# BMS_Carrier_-_AFE_Interface.net
KiCad netlist of a schematic drawn in Altium Designer
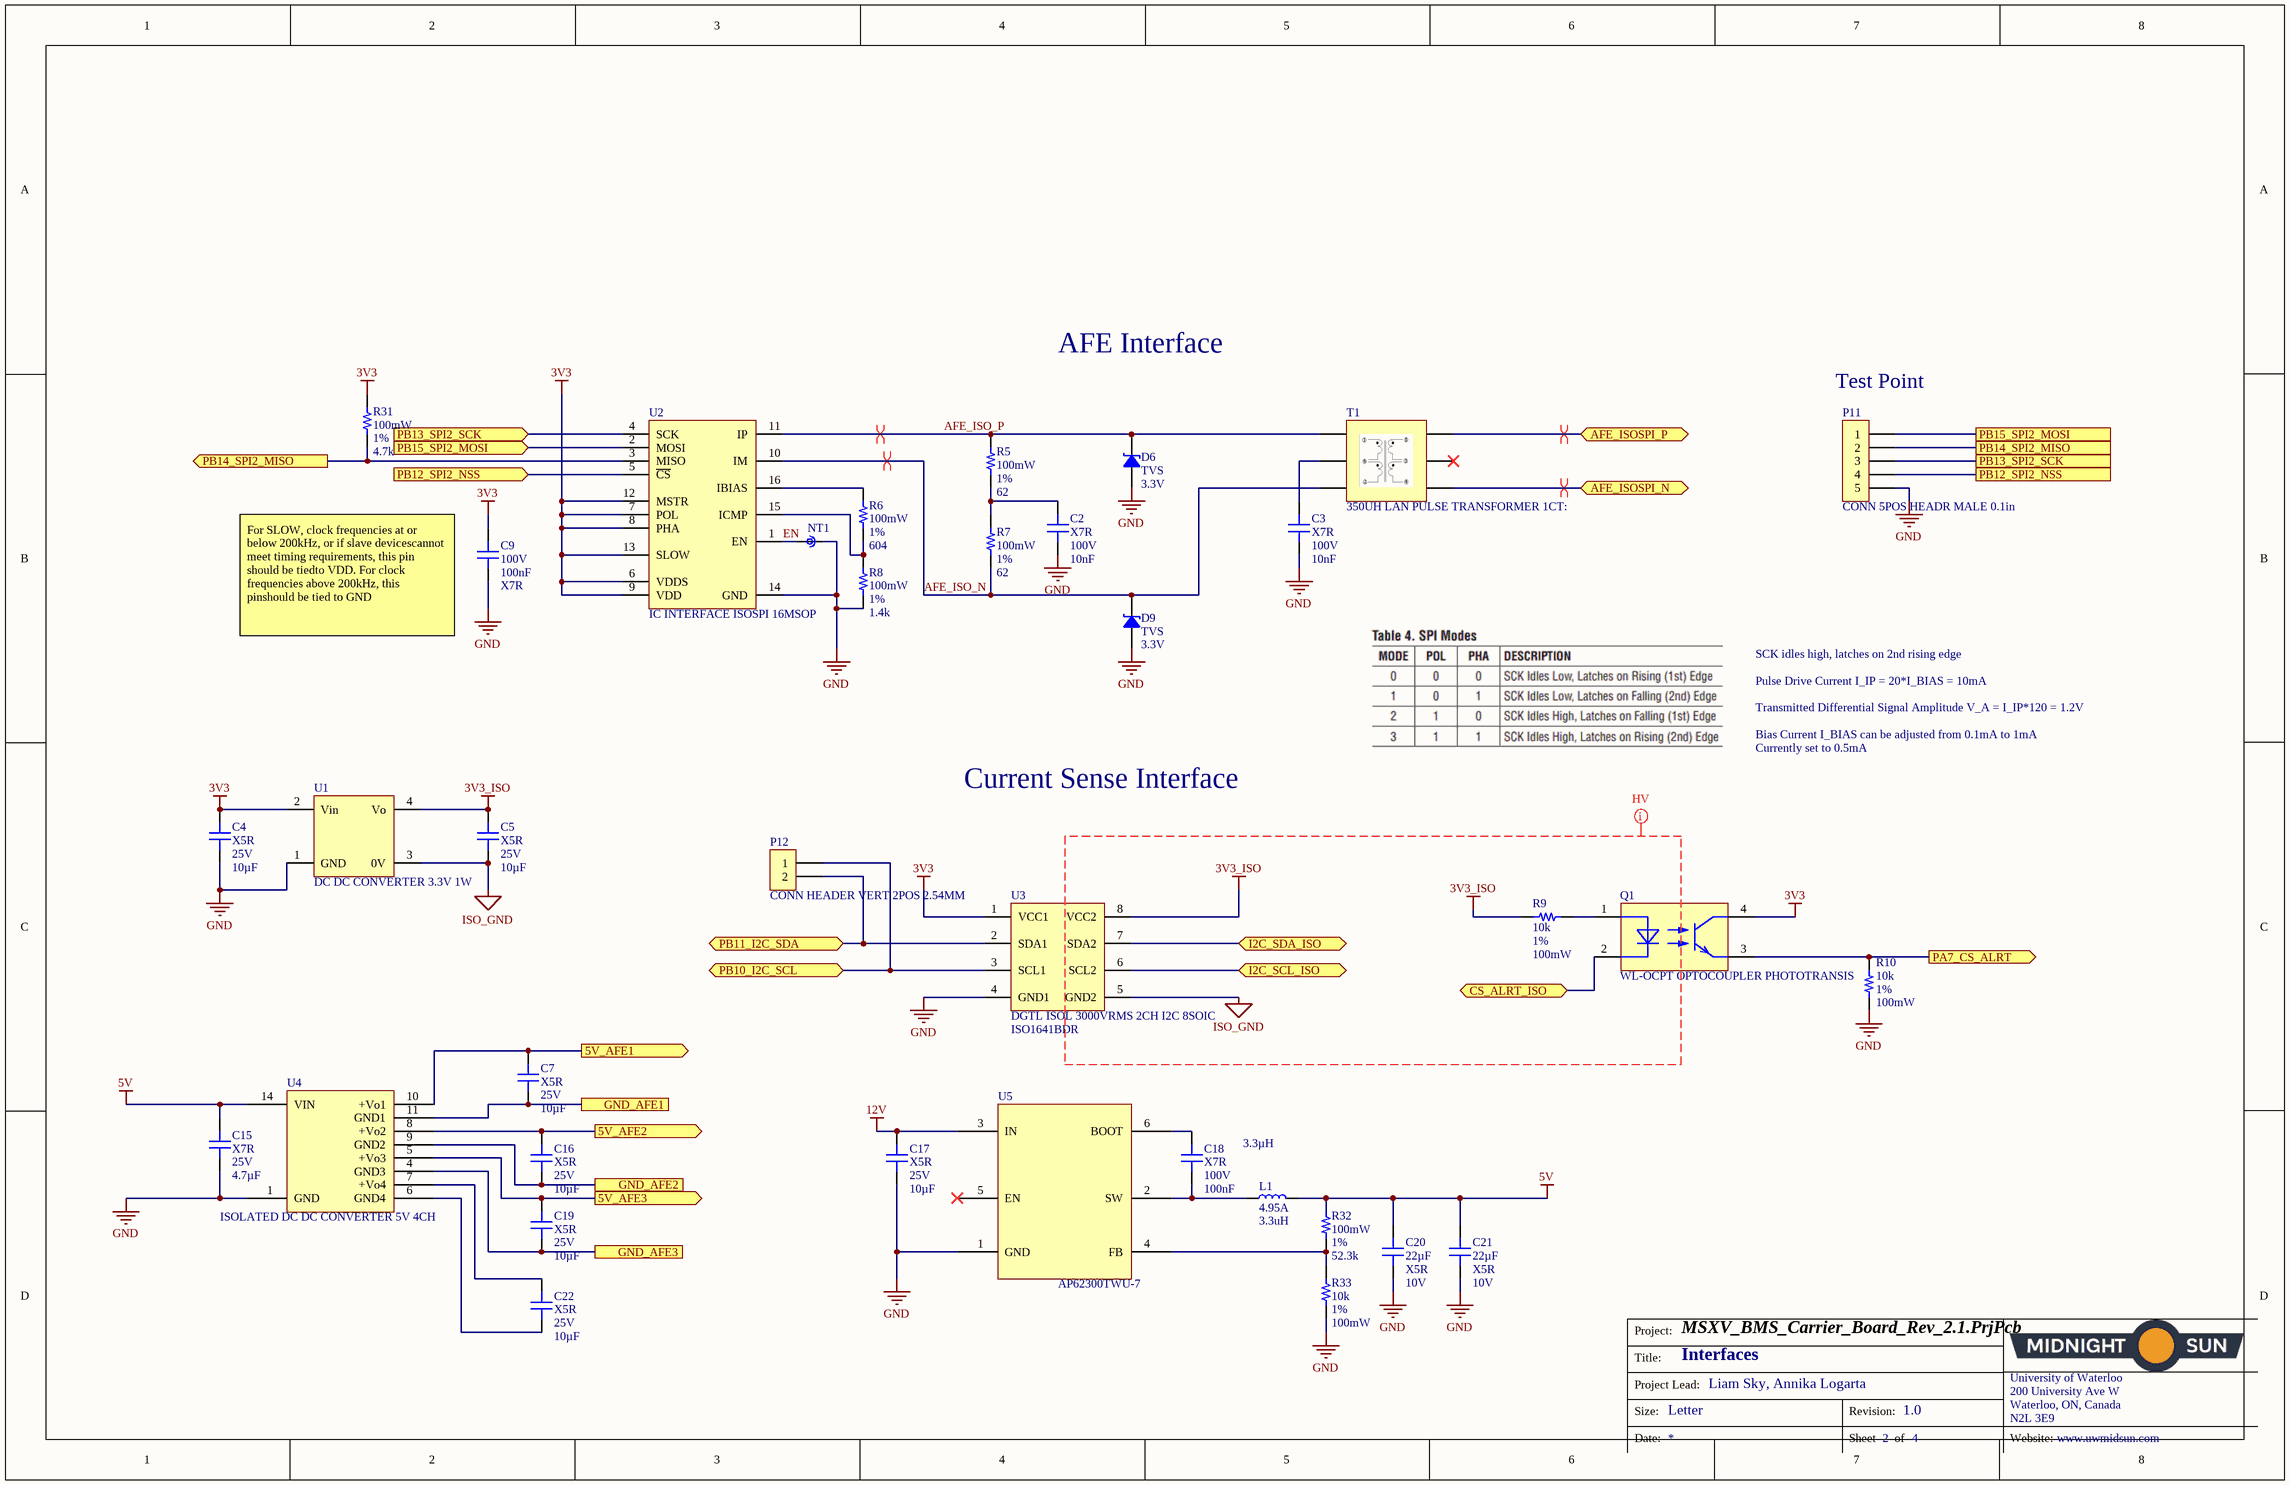
[diagram p0: BMS Carrier - AFE Interface.SchDoc]

(export (version "E")
  (design (tool "Eeschema 10.0.6"))
  (components
    (comp (ref "C2")
      (value "CAP CER 10NF 100V 10% X7R 0603")
      (footprint "CAP 0603_1608")
      (fields
        (field (name "DIELECTRIC CODE") "X7R")
        (field (name "VOLTAGE RATING") "100V")
        (field (name "CAPACITANCE") "10nF")
        (field (name "TOLERANCE") "10%")
      )
      (libsource (lib "Midnight Sun") (part "Capacitor"))
    )
    (comp (ref "C3")
      (value "CAP CER 10NF 100V 10% X7R 0603")
      (footprint "CAP 0603_1608")
      (fields
        (field (name "DIELECTRIC CODE") "X7R")
        (field (name "VOLTAGE RATING") "100V")
        (field (name "CAPACITANCE") "10nF")
        (field (name "TOLERANCE") "10%")
      )
      (libsource (lib "Midnight Sun") (part "Capacitor"))
    )
    (comp (ref "C4")
      (value "CAP CER 10UF 25V 20% X5R 0603")
      (footprint "CAP 0603_1608")
      (description "10µF ±20% 25V Ceramic Capacitor X5R 0603 (1608 Metric)")
      (fields
        (field (name "DIELECTRIC CODE") "X5R")
        (field (name "VOLTAGE RATING") "25V")
        (field (name "CAPACITANCE") "10µF")
        (field (name "TOLERANCE") "20%")
      )
      (libsource (lib "Midnight Sun") (part "Capacitor"))
    )
    (comp (ref "C5")
      (value "CAP CER 10UF 25V 20% X5R 0603")
      (footprint "CAP 0603_1608")
      (description "10µF ±20% 25V Ceramic Capacitor X5R 0603 (1608 Metric)")
      (fields
        (field (name "DIELECTRIC CODE") "X5R")
        (field (name "VOLTAGE RATING") "25V")
        (field (name "CAPACITANCE") "10µF")
        (field (name "TOLERANCE") "20%")
      )
      (libsource (lib "Midnight Sun") (part "Capacitor"))
    )
    (comp (ref "C7")
      (value "CAP CER 10UF 25V 20% X5R 0603")
      (footprint "CAP 0603_1608")
      (description "10µF ±20% 25V Ceramic Capacitor X5R 0603 (1608 Metric)")
      (fields
        (field (name "DIELECTRIC CODE") "X5R")
        (field (name "VOLTAGE RATING") "25V")
        (field (name "CAPACITANCE") "10µF")
        (field (name "TOLERANCE") "20%")
      )
      (libsource (lib "Midnight Sun") (part "Capacitor"))
    )
    (comp (ref "C9")
      (value "CAP CER 0.1UF 100V 10% X7R 0603")
      (footprint "CAP 0603_1608")
      (fields
        (field (name "TOLERANCE") "10%")
        (field (name "VOLTAGE RATING") "100V")
        (field (name "CAPACITANCE") "100nF")
        (field (name "DIELECTRIC CODE") "X7R")
      )
      (libsource (lib "Midnight Sun") (part "Capacitor"))
    )
    (comp (ref "C15")
      (value "CAP CER 4.7UF 25V 10% X5R 0603")
      (footprint "CAP 0603_1608")
      (description "4.7µF ±10% 25V Ceramic Capacitor X5R 0603 (1608 Metric)")
      (fields
        (field (name "DIELECTRIC CODE") "X7R")
        (field (name "VOLTAGE RATING") "25V")
        (field (name "CAPACITANCE") "4.7µF")
        (field (name "TOLERANCE") "10%")
      )
      (libsource (lib "Midnight Sun") (part "Capacitor"))
    )
    (comp (ref "C16")
      (value "CAP CER 10UF 25V 20% X5R 0603")
      (footprint "CAP 0603_1608")
      (description "10µF ±20% 25V Ceramic Capacitor X5R 0603 (1608 Metric)")
      (fields
        (field (name "DIELECTRIC CODE") "X5R")
        (field (name "VOLTAGE RATING") "25V")
        (field (name "CAPACITANCE") "10µF")
        (field (name "TOLERANCE") "20%")
      )
      (libsource (lib "Midnight Sun") (part "Capacitor"))
    )
    (comp (ref "C17")
      (value "CAP CER 10UF 25V 20% X5R 0603")
      (footprint "CAP 0603_1608")
      (description "10µF ±20% 25V Ceramic Capacitor X5R 0603 (1608 Metric)")
      (fields
        (field (name "DIELECTRIC CODE") "X5R")
        (field (name "VOLTAGE RATING") "25V")
        (field (name "CAPACITANCE") "10µF")
        (field (name "TOLERANCE") "20%")
      )
      (libsource (lib "Midnight Sun") (part "Capacitor"))
    )
    (comp (ref "C18")
      (value "CAP CER 0.1UF 100V 10% X7R 0603")
      (footprint "CAP 0603_1608")
      (fields
        (field (name "DIELECTRIC CODE") "X7R")
        (field (name "VOLTAGE RATING") "100V")
        (field (name "CAPACITANCE") "100nF")
        (field (name "TOLERANCE") "10%")
      )
      (libsource (lib "Midnight Sun") (part "Capacitor"))
    )
    (comp (ref "C19")
      (value "CAP CER 10UF 25V 20% X5R 0603")
      (footprint "CAP 0603_1608")
      (description "10µF ±20% 25V Ceramic Capacitor X5R 0603 (1608 Metric)")
      (fields
        (field (name "DIELECTRIC CODE") "X5R")
        (field (name "VOLTAGE RATING") "25V")
        (field (name "CAPACITANCE") "10µF")
        (field (name "TOLERANCE") "20%")
      )
      (libsource (lib "Midnight Sun") (part "Capacitor"))
    )
    (comp (ref "C20")
      (value "CAP CER 22UF 10V 20% X5R 0603")
      (footprint "CAP 0603_1608")
      (fields
        (field (name "CAPACITANCE") "22µF")
        (field (name "TOLERANCE") "20%")
        (field (name "DIELECTRIC CODE") "X5R")
        (field (name "VOLTAGE RATING") "10V")
      )
      (libsource (lib "Midnight Sun") (part "Capacitor"))
    )
    (comp (ref "C21")
      (value "CAP CER 22UF 10V 20% X5R 0603")
      (footprint "CAP 0603_1608")
      (fields
        (field (name "CAPACITANCE") "22µF")
        (field (name "TOLERANCE") "20%")
        (field (name "DIELECTRIC CODE") "X5R")
        (field (name "VOLTAGE RATING") "10V")
      )
      (libsource (lib "Midnight Sun") (part "Capacitor"))
    )
    (comp (ref "C22")
      (value "CAP CER 10UF 25V 20% X5R 0603")
      (footprint "CAP 0603_1608")
      (description "10µF ±20% 25V Ceramic Capacitor X5R 0603 (1608 Metric)")
      (fields
        (field (name "DIELECTRIC CODE") "X5R")
        (field (name "VOLTAGE RATING") "25V")
        (field (name "CAPACITANCE") "10µF")
        (field (name "TOLERANCE") "20%")
      )
      (libsource (lib "Midnight Sun") (part "Capacitor"))
    )
    (comp (ref "D6")
      (value "TVS DIODE 3.3VWM 10VC SOD323")
      (footprint "SOD 323")
      (description "Trans Voltage Suppressor Diode, 3.3V V(RWM), Unidirectional, 1 Element, Silicon")
      (fields (field (name "TYPE") "TVS") (field (name "REVERSE BLOCKING VOLTAGE") "3.3V"))
      (libsource (lib "Midnight Sun") (part "Diode Zener/TVS"))
    )
    (comp (ref "D9")
      (value "TVS DIODE 3.3VWM 10VC SOD323")
      (footprint "SOD 323")
      (description "Trans Voltage Suppressor Diode, 3.3V V(RWM), Unidirectional, 1 Element, Silicon")
      (fields (field (name "TYPE") "TVS") (field (name "REVERSE BLOCKING VOLTAGE") "3.3V"))
      (libsource (lib "Midnight Sun") (part "Diode Zener/TVS"))
    )
    (comp (ref "L1")
      (value "3.3µH")
      (footprint "INDUCTOR TDK 6x6")
      (description "General Purpose Inductor, 3.3uH, 30%, 1 Element, Ferrite-Core, SMD, 2424")
      (fields
        (field (name "RATED CURRENT-MAX") "4.95A")
        (field (name "INDUCTANCE-NOM (L)") "3.3uH")
        (field (name "TOLERANCE") "30%")
        (field (name "Comment") "FIXED IND 3.3UH 4.95A 30MOHM SMD")
      )
      (libsource (lib "Midnight Sun") (part "FIXED IND 3.3UH 4.95A 30MOHM SMD"))
    )
    (comp (ref "NT1")
      (value "Net Tie 5mil")
      (footprint "Net Tie")
      (libsource (lib "Midnight Sun") (part "Net Tie"))
    )
    (comp (ref "P11")
      (value "CONN 5POS HEADR MALE 0.1in")
      (footprint "CONN, 5POS HEADR 0.1\"")
      (description "5 Positions Header, Breakaway Connector 0.100\" (2.54mm) Through Hole Tin")
      (fields (field (name "SOURCE") "Schematic Diagrams.SchLib"))
      (libsource (lib "Midnight Sun") (part "CONN 5POS HEADR MALE 0.1in"))
    )
    (comp (ref "P12")
      (value "CONN HEADER VERT 2POS 2.54MM")
      (footprint "HDR1X2")
      (description "Connector Header Through Hole 2 position 0.100\" (2.54mm)")
      (libsource (lib "Midnight Sun") (part "CONN 2POS"))
    )
    (comp (ref "Q1")
      (value "WL-OCPT OPTOCOUPLER PHOTOTRANSIS")
      (footprint "WL-OCPT_LSOP4")
      (description "Optocoupler, Transistor, 80V, Lsop-4 Rohs Compliant: Yes")
      (libsource (lib "Midnight Sun") (part "Optocoupler Phototransistor_DC_1 Channel"))
    )
    (comp (ref "R5")
      (value "RES 62 OHM 1% 1/10W 0603")
      (footprint "RES 0603_1608")
      (fields
        (field (name "POWER RATING") "100mW")
        (field (name "TOLERANCE") "1%")
        (field (name "RESISTANCE") "62")
      )
      (libsource (lib "Midnight Sun") (part "Resistor"))
    )
    (comp (ref "R6")
      (value "RES 604 OHM 1% 1/10W 0603")
      (footprint "RES 0603_1608")
      (fields
        (field (name "POWER RATING") "100mW")
        (field (name "TOLERANCE") "1%")
        (field (name "RESISTANCE") "604")
      )
      (libsource (lib "Midnight Sun") (part "Resistor"))
    )
    (comp (ref "R7")
      (value "RES 62 OHM 1% 1/10W 0603")
      (footprint "RES 0603_1608")
      (fields
        (field (name "POWER RATING") "100mW")
        (field (name "TOLERANCE") "1%")
        (field (name "RESISTANCE") "62")
      )
      (libsource (lib "Midnight Sun") (part "Resistor"))
    )
    (comp (ref "R8")
      (value "RES 1.4K OHM 1% 1/10W 0603")
      (footprint "RES 0603_1608")
      (fields
        (field (name "POWER RATING") "100mW")
        (field (name "TOLERANCE") "1%")
        (field (name "RESISTANCE") "1.4k")
      )
      (libsource (lib "Midnight Sun") (part "Resistor"))
    )
    (comp (ref "R9")
      (value "RES 10K OHM 1% 1/10W 0603")
      (footprint "RES 0603_1608")
      (description "10 ±1% 0.1W, 1/10W Chip Resistor 0603 (1608 Metric) Automotive AEC-Q200 Thick Film")
      (fields
        (field (name "RESISTANCE") "10k")
        (field (name "TOLERANCE") "1%")
        (field (name "POWER RATING") "100mW")
      )
      (libsource (lib "Midnight Sun") (part "Resistor"))
    )
    (comp (ref "R10")
      (value "RES 10K OHM 1% 1/10W 0603")
      (footprint "RES 0603_1608")
      (description "10 ±1% 0.1W, 1/10W Chip Resistor 0603 (1608 Metric) Automotive AEC-Q200 Thick Film")
      (fields
        (field (name "RESISTANCE") "10k")
        (field (name "TOLERANCE") "1%")
        (field (name "POWER RATING") "100mW")
      )
      (libsource (lib "Midnight Sun") (part "Resistor"))
    )
    (comp (ref "R31")
      (value "RES 4.7K OHM 1% 1/10W 0603")
      (footprint "RES 0603_1608")
      (fields
        (field (name "POWER RATING") "100mW")
        (field (name "TOLERANCE") "1%")
        (field (name "RESISTANCE") "4.7k")
      )
      (libsource (lib "Midnight Sun") (part "Resistor"))
    )
    (comp (ref "R32")
      (value "RES 52.3K OHM 1% 1/10W 0603")
      (footprint "RES 0603_1608")
      (fields
        (field (name "POWER RATING") "100mW")
        (field (name "TOLERANCE") "1%")
        (field (name "RESISTANCE") "52.3k")
      )
      (libsource (lib "Midnight Sun") (part "Resistor"))
    )
    (comp (ref "R33")
      (value "RES 10K OHM 1% 1/10W 0603")
      (footprint "RES 0603_1608")
      (description "10 ±1% 0.1W, 1/10W Chip Resistor 0603 (1608 Metric) Automotive AEC-Q200 Thick Film")
      (fields
        (field (name "RESISTANCE") "10k")
        (field (name "TOLERANCE") "1%")
        (field (name "POWER RATING") "100mW")
      )
      (libsource (lib "Midnight Sun") (part "Resistor"))
    )
    (comp (ref "T1")
      (value "350UH LAN PULSE TRANSFORMER 1CT:")
      (footprint "TXF453229NF-121-Footprint-1")
      (description "350µH LAN Pulse Transformer 1:1 Surface Mount")
      (libsource (lib "Midnight Sun") (part "TXF453229NF-121"))
    )
    (comp (ref "U1")
      (value "DC DC CONVERTER 3.3V 1W")
      (footprint "DCDC ISOLATED 12V 1W-Footprint-1")
      (description "DC DC Converter 3.3V 1W")
      (libsource (lib "Midnight Sun") (part "DCDC ISOLATED 3.3V 1W"))
    )
    (comp (ref "U2")
      (value "IC INTERFACE ISOSPI 16MSOP")
      (footprint "MSOP 16")
      (description "Isolated Communications Interface 3.3V/5V Automotive 16-Pin MSOP Tube")
      (fields (field (name "MANUFACTURER PART NUMBER") "LTC6820IMS#PBF"))
      (libsource (lib "Midnight Sun") (part "LT-LTC6820-MS-16"))
    )
    (comp (ref "U3")
      (value "DGTL ISOL 3000VRMS 2CH I2C 8SOIC")
      (footprint "SOIC 8")
      (description "I²C Digital Isolator 3000Vrms 2 Channel 1Mbps 50kV/µs CMTI 8-SOIC (0.154\", 3.90mm Width)")
      (fields (field (name "MANUFACTURER PART NUMBER") "ISO1641BDR"))
      (libsource (lib "Midnight Sun") (part "DGTL ISOL 2500VRMS 2CH I2C 8SOIC-Symbol-1"))
    )
    (comp (ref "U4")
      (value "ISOLATED DC DC CONVERTER 5V 4CH")
      (footprint "DIP14")
      (description "Isolated Module DC DC Converter 4 Output 5V 5V 5V 5V 50mA, 50mA, 50mA, 50mA 4.5V - 5.5V Input")
      (libsource (lib "Midnight Sun") (part "J0505N-1WR3"))
    )
    (comp (ref "U5")
      (value "CMP-031-00049-1")
      (footprint "TSOT26")
      (description "Buck Switching Regulator IC Positive Adjustable 0.8V 1 Output 3A SOT-23-6 Thin, TSOT-23-6")
      (fields (field (name "MANUFACTURER") "Diodes") (field (name "MANUFACTURER PART NUMBER") "AP62300TWU-7"))
      (libsource (lib "Midnight Sun") (part "IC REG BUCK ADJ 3A TSOT26"))
    )
  )
  (nets
    (net (code "1") (name "/5V_AFE1") (class "Default")
      (node (ref "C7") (pin "2") (pinfunction "2_2") (pintype "passive"))
      (node (ref "U4") (pin "10") (pinfunction "+Vo1_10") (pintype "passive"))
    )
    (net (code "2") (name "/5V_AFE2") (class "Default")
      (node (ref "C16") (pin "2") (pinfunction "2_2") (pintype "passive"))
      (node (ref "U4") (pin "8") (pinfunction "+Vo2_8") (pintype "passive"))
    )
    (net (code "3") (name "/5V_AFE3") (class "Default")
      (node (ref "C19") (pin "2") (pinfunction "2_2") (pintype "passive"))
      (node (ref "U4") (pin "5") (pinfunction "+Vo3_5") (pintype "passive"))
    )
    (net (code "4") (name "/AFE_ISOSPI_N") (class "Default")
      (node (ref "T1") (pin "4") (pinfunction "2_4") (pintype "passive"))
    )
    (net (code "5") (name "/AFE_ISOSPI_P") (class "Default")
      (node (ref "T1") (pin "5") (pinfunction "0_5") (pintype "passive"))
    )
    (net (code "6") (name "/AFE_ISO_N") (class "Default")
      (node (ref "D9") (pin "1") (pinfunction "1_1") (pintype "passive"))
      (node (ref "R7") (pin "1") (pinfunction "1_1") (pintype "passive"))
      (node (ref "T1") (pin "2") (pinfunction "5_2") (pintype "passive"))
      (node (ref "U2") (pin "10") (pinfunction "IM_10") (pintype "passive"))
    )
    (net (code "7") (name "/AFE_ISO_P") (class "Default")
      (node (ref "D6") (pin "1") (pinfunction "1_1") (pintype "passive"))
      (node (ref "R5") (pin "2") (pinfunction "2_2") (pintype "passive"))
      (node (ref "T1") (pin "1") (pinfunction "3_1") (pintype "passive"))
      (node (ref "U2") (pin "11") (pinfunction "IP_11") (pintype "passive"))
    )
    (net (code "8") (name "/CS_ALRT_ISO") (class "Default")
      (node (ref "Q1") (pin "2") (pinfunction "Cathode_2") (pintype "passive"))
    )
    (net (code "9") (name "/EN") (class "Default")
      (node (ref "NT1") (pin "1") (pinfunction "1_1") (pintype "passive"))
      (node (ref "U2") (pin "1") (pinfunction "EN_1") (pintype "passive"))
    )
    (net (code "10") (name "/GND_AFE1") (class "Default")
      (node (ref "C7") (pin "1") (pinfunction "1_1") (pintype "passive"))
      (node (ref "U4") (pin "11") (pinfunction "GND1_11") (pintype "passive"))
    )
    (net (code "11") (name "/GND_AFE2") (class "Default")
      (node (ref "C16") (pin "1") (pinfunction "1_1") (pintype "passive"))
      (node (ref "U4") (pin "9") (pinfunction "GND2_9") (pintype "passive"))
    )
    (net (code "12") (name "/GND_AFE3") (class "Default")
      (node (ref "C19") (pin "1") (pinfunction "1_1") (pintype "passive"))
      (node (ref "U4") (pin "4") (pinfunction "GND3_4") (pintype "passive"))
    )
    (net (code "13") (name "/I2C_SCL_ISO") (class "Default")
      (node (ref "U3") (pin "6") (pinfunction "SCL2_6") (pintype "passive"))
    )
    (net (code "14") (name "/I2C_SDA_ISO") (class "Default")
      (node (ref "U3") (pin "7") (pinfunction "SDA2_7") (pintype "passive"))
    )
    (net (code "15") (name "/PA7_CS_ALRT") (class "Default")
      (node (ref "Q1") (pin "3") (pinfunction "Emitter_3") (pintype "passive"))
      (node (ref "R10") (pin "2") (pinfunction "2_2") (pintype "passive"))
    )
    (net (code "16") (name "/PB10_I2C_SCL") (class "Default")
      (node (ref "P12") (pin "1") (pinfunction "1_1") (pintype "passive"))
      (node (ref "U3") (pin "3") (pinfunction "SCL1_3") (pintype "passive"))
    )
    (net (code "17") (name "/PB11_I2C_SDA") (class "Default")
      (node (ref "P12") (pin "2") (pinfunction "2_2") (pintype "passive"))
      (node (ref "U3") (pin "2") (pinfunction "SDA1_2") (pintype "passive"))
    )
    (net (code "18") (name "/PB12_SPI2_NSS") (class "Default")
      (node (ref "P11") (pin "4") (pinfunction "4_4") (pintype "passive"))
      (node (ref "U2") (pin "5") (pinfunction "~{CS}_5") (pintype "passive"))
    )
    (net (code "19") (name "/PB13_SPI2_SCK") (class "Default")
      (node (ref "P11") (pin "3") (pinfunction "3_3") (pintype "passive"))
      (node (ref "U2") (pin "4") (pinfunction "SCK_4") (pintype "passive"))
    )
    (net (code "20") (name "/PB14_SPI2_MISO") (class "Default")
      (node (ref "P11") (pin "2") (pinfunction "2_2") (pintype "passive"))
      (node (ref "R31") (pin "2") (pinfunction "2_2") (pintype "passive"))
      (node (ref "U2") (pin "3") (pinfunction "MISO_3") (pintype "passive"))
    )
    (net (code "21") (name "/PB15_SPI2_MOSI") (class "Default")
      (node (ref "P11") (pin "1") (pinfunction "1_1") (pintype "passive"))
      (node (ref "U2") (pin "2") (pinfunction "MOSI_2") (pintype "passive"))
    )
    (net (code "22") (name "3V3") (class "Default")
      (node (ref "C4") (pin "2") (pinfunction "2_2") (pintype "passive"))
      (node (ref "C9") (pin "2") (pinfunction "2_2") (pintype "passive"))
      (node (ref "Q1") (pin "4") (pinfunction "Collector_4") (pintype "passive"))
      (node (ref "R31") (pin "1") (pinfunction "1_1") (pintype "passive"))
      (node (ref "U1") (pin "2") (pinfunction "Vin_2") (pintype "passive"))
      (node (ref "U2") (pin "12") (pinfunction "MSTR_12") (pintype "passive"))
      (node (ref "U2") (pin "13") (pinfunction "SLOW_13") (pintype "passive"))
      (node (ref "U2") (pin "6") (pinfunction "VDDS_6") (pintype "passive"))
      (node (ref "U2") (pin "7") (pinfunction "POL_7") (pintype "passive"))
      (node (ref "U2") (pin "8") (pinfunction "PHA_8") (pintype "passive"))
      (node (ref "U2") (pin "9") (pinfunction "VDD_9") (pintype "passive"))
      (node (ref "U3") (pin "1") (pinfunction "VCC1_1") (pintype "passive"))
    )
    (net (code "23") (name "3V3_ISO") (class "Default")
      (node (ref "C5") (pin "2") (pinfunction "2_2") (pintype "passive"))
      (node (ref "R9") (pin "2") (pinfunction "2_2") (pintype "passive"))
      (node (ref "U1") (pin "4") (pinfunction "Vo_4") (pintype "passive"))
      (node (ref "U3") (pin "8") (pinfunction "VCC2_8") (pintype "passive"))
    )
    (net (code "24") (name "5V") (class "Default")
      (node (ref "C15") (pin "1") (pinfunction "1_1") (pintype "passive"))
      (node (ref "C20") (pin "2") (pinfunction "2_2") (pintype "passive"))
      (node (ref "C21") (pin "2") (pinfunction "2_2") (pintype "passive"))
      (node (ref "L1") (pin "2") (pintype "passive"))
      (node (ref "R32") (pin "2") (pinfunction "2_2") (pintype "passive"))
      (node (ref "U4") (pin "14") (pinfunction "VIN_14") (pintype "passive"))
    )
    (net (code "25") (name "12V") (class "Default")
      (node (ref "C17") (pin "2") (pinfunction "2_2") (pintype "passive"))
      (node (ref "U5") (pin "3") (pinfunction "IN_3") (pintype "passive"))
    )
    (net (code "26") (name "GND") (class "Default")
      (node (ref "C15") (pin "2") (pinfunction "2_2") (pintype "passive"))
      (node (ref "C17") (pin "1") (pinfunction "1_1") (pintype "passive"))
      (node (ref "C2") (pin "1") (pinfunction "1_1") (pintype "passive"))
      (node (ref "C20") (pin "1") (pinfunction "1_1") (pintype "passive"))
      (node (ref "C21") (pin "1") (pinfunction "1_1") (pintype "passive"))
      (node (ref "C3") (pin "1") (pinfunction "1_1") (pintype "passive"))
      (node (ref "C4") (pin "1") (pinfunction "1_1") (pintype "passive"))
      (node (ref "C9") (pin "1") (pinfunction "1_1") (pintype "passive"))
      (node (ref "D6") (pin "2") (pinfunction "2_2") (pintype "passive"))
      (node (ref "D9") (pin "2") (pinfunction "2_2") (pintype "passive"))
      (node (ref "NT1") (pin "2") (pinfunction "2_2") (pintype "passive"))
      (node (ref "P11") (pin "5") (pinfunction "5_5") (pintype "passive"))
      (node (ref "R10") (pin "1") (pinfunction "1_1") (pintype "passive"))
      (node (ref "R33") (pin "1") (pinfunction "1_1") (pintype "passive"))
      (node (ref "R8") (pin "1") (pinfunction "1_1") (pintype "passive"))
      (node (ref "U1") (pin "1") (pinfunction "GND_1") (pintype "passive"))
      (node (ref "U2") (pin "14") (pinfunction "GND_14") (pintype "passive"))
      (node (ref "U3") (pin "4") (pinfunction "GND1_4") (pintype "passive"))
      (node (ref "U4") (pin "1") (pinfunction "GND_1") (pintype "passive"))
      (node (ref "U5") (pin "1") (pinfunction "GND_1") (pintype "passive"))
    )
    (net (code "27") (name "ISO_GND") (class "Default")
      (node (ref "C5") (pin "1") (pinfunction "1_1") (pintype "passive"))
      (node (ref "U1") (pin "3") (pinfunction "0V_3") (pintype "passive"))
      (node (ref "U3") (pin "5") (pinfunction "GND2_5") (pintype "passive"))
    )
    (net (code "28") (name "Net-(C2-Pad2)") (class "Default")
      (node (ref "C2") (pin "2") (pinfunction "2_2") (pintype "passive"))
      (node (ref "R5") (pin "1") (pinfunction "1_1") (pintype "passive"))
      (node (ref "R7") (pin "2") (pinfunction "2_2") (pintype "passive"))
    )
    (net (code "29") (name "Net-(Q1-Anode)") (class "Default")
      (node (ref "Q1") (pin "1") (pinfunction "Anode_1") (pintype "passive"))
      (node (ref "R9") (pin "1") (pinfunction "1_1") (pintype "passive"))
    )
    (net (code "30") (name "Net-(T1-4)") (class "Default")
      (node (ref "C3") (pin "2") (pinfunction "2_2") (pintype "passive"))
      (node (ref "T1") (pin "6") (pinfunction "4_6") (pintype "passive"))
    )
    (net (code "31") (name "Net-(U2-IBIAS)") (class "Default")
      (node (ref "R6") (pin "2") (pinfunction "2_2") (pintype "passive"))
      (node (ref "U2") (pin "16") (pinfunction "IBIAS_16") (pintype "passive"))
    )
    (net (code "32") (name "Net-(U2-ICMP)") (class "Default")
      (node (ref "R6") (pin "1") (pinfunction "1_1") (pintype "passive"))
      (node (ref "R8") (pin "2") (pinfunction "2_2") (pintype "passive"))
      (node (ref "U2") (pin "15") (pinfunction "ICMP_15") (pintype "passive"))
    )
    (net (code "33") (name "Net-(U4-+Vo4)") (class "Default")
      (node (ref "C22") (pin "2") (pinfunction "2_2") (pintype "passive"))
      (node (ref "U4") (pin "7") (pinfunction "+Vo4_7") (pintype "passive"))
    )
    (net (code "34") (name "Net-(U4-GND4)") (class "Default")
      (node (ref "C22") (pin "1") (pinfunction "1_1") (pintype "passive"))
      (node (ref "U4") (pin "6") (pinfunction "GND4_6") (pintype "passive"))
    )
    (net (code "35") (name "Net-(U5-BOOT)") (class "Default")
      (node (ref "C18") (pin "2") (pinfunction "2_2") (pintype "passive"))
      (node (ref "U5") (pin "6") (pinfunction "BOOT_6") (pintype "passive"))
    )
    (net (code "36") (name "Net-(U5-FB)") (class "Default")
      (node (ref "R32") (pin "1") (pinfunction "1_1") (pintype "passive"))
      (node (ref "R33") (pin "2") (pinfunction "2_2") (pintype "passive"))
      (node (ref "U5") (pin "4") (pinfunction "FB_4") (pintype "passive"))
    )
    (net (code "37") (name "Net-(U5-SW)") (class "Default")
      (node (ref "C18") (pin "1") (pinfunction "1_1") (pintype "passive"))
      (node (ref "L1") (pin "1") (pintype "passive"))
      (node (ref "U5") (pin "2") (pinfunction "SW_2") (pintype "passive"))
    )
    (net (code "38") (name "unconnected-(T1-1-Pad3)") (class "Default")
      (node (ref "T1") (pin "3") (pinfunction "1_3") (pintype "passive+no_connect"))
    )
    (net (code "39") (name "unconnected-(U5-EN-Pad5)") (class "Default")
      (node (ref "U5") (pin "5") (pinfunction "EN_5") (pintype "passive+no_connect"))
    )
  )
)
